# Board4.net
KiCad netlist of a schematic drawn in Altium Designer
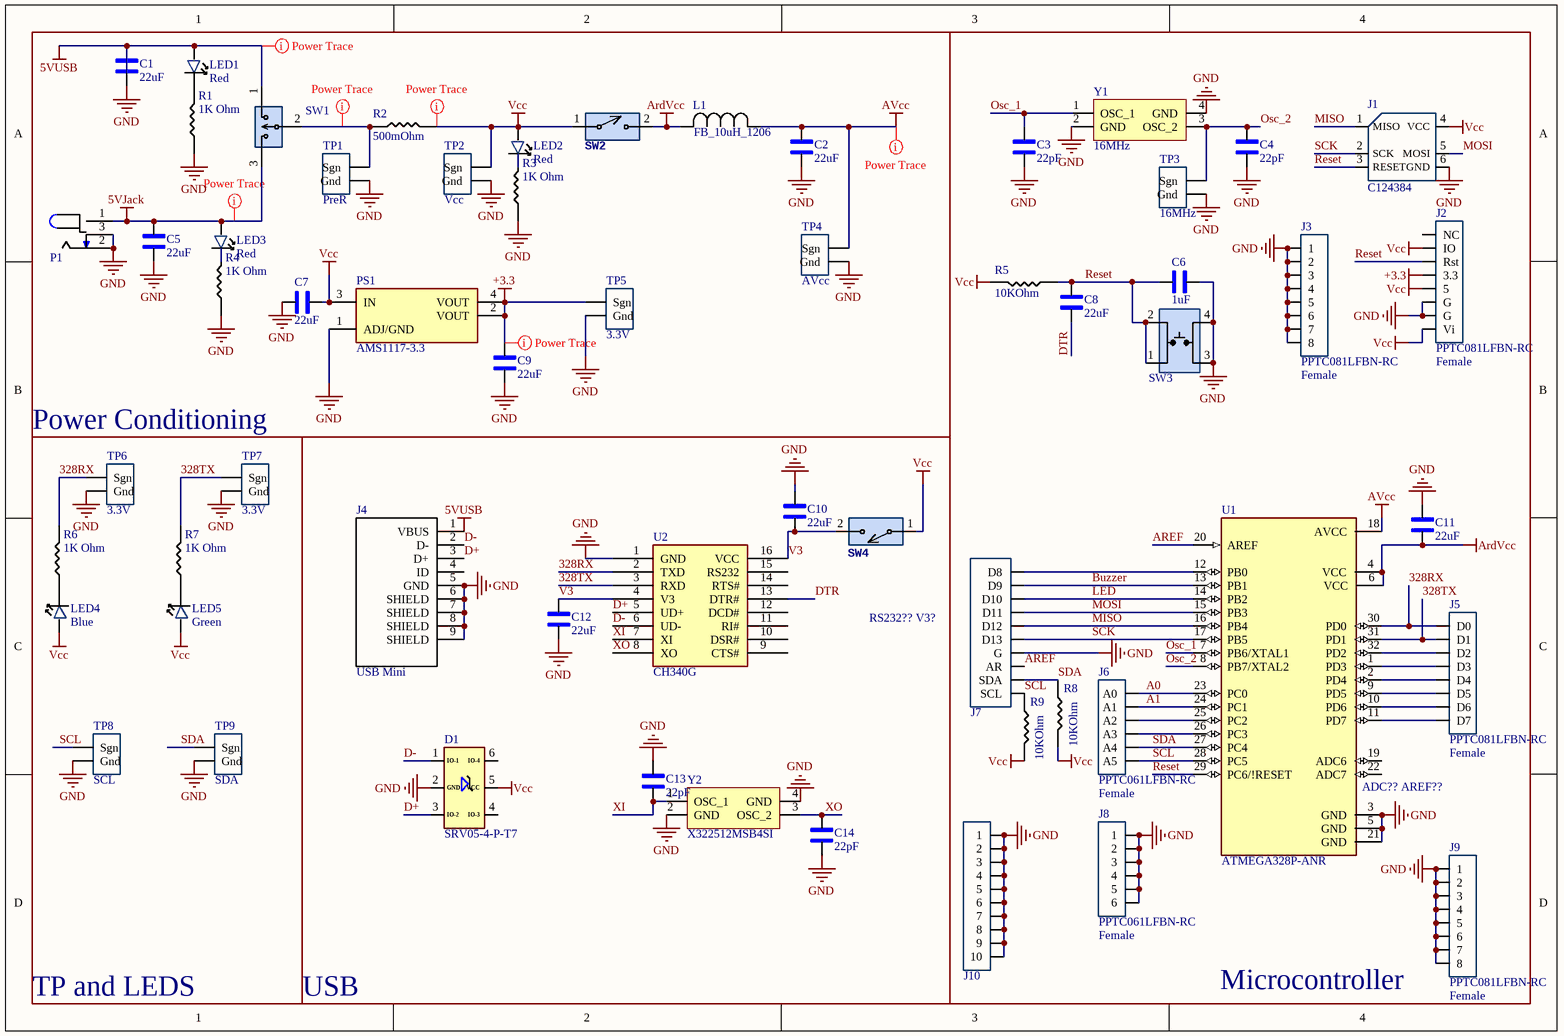
[diagram p0: Board4.SchDoc]

(export (version "E")
  (design (tool "Eeschema 10.0.6"))
  (components
    (comp (ref "C1")
      (value "22uF")
      (footprint "1206_Passive_Capacitor")
      (description "22uF ±10% 25V X5R 1206 Multilayer Ceramic Capacitors MLCC - SMD/SMT RoHS")
      (fields (field (name "MFR PART #") "CL31A226KAHNNNE") (field (name "LCSC PART#") "C12891"))
      (libsource (lib "ECEN5730Lib_2023_01_DS") (part "C_22uF_1206"))
    )
    (comp (ref "C2")
      (value "22uF")
      (footprint "1206_Passive_Capacitor")
      (description "22uF ±10% 25V X5R 1206 Multilayer Ceramic Capacitors MLCC - SMD/SMT RoHS")
      (fields (field (name "MFR PART #") "CL31A226KAHNNNE") (field (name "LCSC PART#") "C12891"))
      (libsource (lib "ECEN5730Lib_2023_01_DS") (part "C_22uF_1206"))
    )
    (comp (ref "C3")
      (value "22pF")
      (footprint "1206_Passive_Capacitor")
      (description "22pF ±5% 1kV C0G 1206 Multilayer Ceramic Capacitors MLCC - SMD/SMT RoHS")
      (fields (field (name "LCSC PART#") "C313096") (field (name "MFR PART #") "1206CG220J102NT"))
      (libsource (lib "ECEN5730Lib_2023_01_DS") (part "C_22pF_1206"))
    )
    (comp (ref "C4")
      (value "22pF")
      (footprint "1206_Passive_Capacitor")
      (description "22pF ±5% 1kV C0G 1206 Multilayer Ceramic Capacitors MLCC - SMD/SMT RoHS")
      (fields (field (name "LCSC PART#") "C313096") (field (name "MFR PART #") "1206CG220J102NT"))
      (libsource (lib "ECEN5730Lib_2023_01_DS") (part "C_22pF_1206"))
    )
    (comp (ref "C5")
      (value "22uF")
      (footprint "1206_Passive_Capacitor")
      (description "22uF ±10% 25V X5R 1206 Multilayer Ceramic Capacitors MLCC - SMD/SMT RoHS")
      (fields (field (name "MFR PART #") "CL31A226KAHNNNE") (field (name "LCSC PART#") "C12891"))
      (libsource (lib "ECEN5730Lib_2023_01_DS") (part "C_22uF_1206"))
    )
    (comp (ref "C6")
      (value "1uF")
      (footprint "1206_Passive_Capacitor")
      (description "MULTILAYER CERAMIC CAPACITORS MLCC - SMD/SMT 1UF 50V 1206 ROHS")
      (fields (field (name "MFR PART #") "CL31B105KBHNNNE") (field (name "LCSC PART#") "C1848"))
      (libsource (lib "ECEN5730Lib_2023_01_DS") (part "C_1uF_1206"))
    )
    (comp (ref "C7")
      (value "22uF")
      (footprint "1206_Passive_Capacitor")
      (description "22uF ±10% 25V X5R 1206 Multilayer Ceramic Capacitors MLCC - SMD/SMT RoHS")
      (fields (field (name "MFR PART #") "CL31A226KAHNNNE") (field (name "LCSC PART#") "C12891"))
      (libsource (lib "ECEN5730Lib_2023_01_DS") (part "C_22uF_1206"))
    )
    (comp (ref "C8")
      (value "22uF")
      (footprint "1206_Passive_Capacitor")
      (description "22uF ±10% 25V X5R 1206 Multilayer Ceramic Capacitors MLCC - SMD/SMT RoHS")
      (fields (field (name "MFR PART #") "CL31A226KAHNNNE") (field (name "LCSC PART#") "C12891"))
      (libsource (lib "ECEN5730Lib_2023_01_DS") (part "C_22uF_1206"))
    )
    (comp (ref "C9")
      (value "22uF")
      (footprint "1206_Passive_Capacitor")
      (description "22uF ±10% 25V X5R 1206 Multilayer Ceramic Capacitors MLCC - SMD/SMT RoHS")
      (fields (field (name "MFR PART #") "CL31A226KAHNNNE") (field (name "LCSC PART#") "C12891"))
      (libsource (lib "ECEN5730Lib_2023_01_DS") (part "C_22uF_1206"))
    )
    (comp (ref "C10")
      (value "22uF")
      (footprint "1206_Passive_Capacitor")
      (description "22uF ±10% 25V X5R 1206 Multilayer Ceramic Capacitors MLCC - SMD/SMT RoHS")
      (fields (field (name "MFR PART #") "CL31A226KAHNNNE") (field (name "LCSC PART#") "C12891"))
      (libsource (lib "ECEN5730Lib_2023_01_DS") (part "C_22uF_1206"))
    )
    (comp (ref "C11")
      (value "22uF")
      (footprint "1206_Passive_Capacitor")
      (description "22uF ±10% 25V X5R 1206 Multilayer Ceramic Capacitors MLCC - SMD/SMT RoHS")
      (fields (field (name "MFR PART #") "CL31A226KAHNNNE") (field (name "LCSC PART#") "C12891"))
      (libsource (lib "ECEN5730Lib_2023_01_DS") (part "C_22uF_1206"))
    )
    (comp (ref "C12")
      (value "22uF")
      (footprint "1206_Passive_Capacitor")
      (description "22uF ±10% 25V X5R 1206 Multilayer Ceramic Capacitors MLCC - SMD/SMT RoHS")
      (fields (field (name "MFR PART #") "CL31A226KAHNNNE") (field (name "LCSC PART#") "C12891"))
      (libsource (lib "ECEN5730Lib_2023_01_DS") (part "C_22uF_1206"))
    )
    (comp (ref "C13")
      (value "22pF")
      (footprint "1206_Passive_Capacitor")
      (description "22pF ±5% 1kV C0G 1206 Multilayer Ceramic Capacitors MLCC - SMD/SMT RoHS")
      (fields (field (name "LCSC PART#") "C313096") (field (name "MFR PART #") "1206CG220J102NT"))
      (libsource (lib "ECEN5730Lib_2023_01_DS") (part "C_22pF_1206"))
    )
    (comp (ref "C14")
      (value "22pF")
      (footprint "1206_Passive_Capacitor")
      (description "22pF ±5% 1kV C0G 1206 Multilayer Ceramic Capacitors MLCC - SMD/SMT RoHS")
      (fields (field (name "LCSC PART#") "C313096") (field (name "MFR PART #") "1206CG220J102NT"))
      (libsource (lib "ECEN5730Lib_2023_01_DS") (part "C_22pF_1206"))
    )
    (comp (ref "D1")
      (value "SRV05-4-P-T7")
      (footprint "TVS")
      (description "TVS SOT-23-6 ROHS")
      (fields (field (name "LCSC PART#") "C85364"))
      (libsource (lib "ECEN5730Lib_2023_01_DS") (part "D_TVS_Diode"))
    )
    (comp (ref "J1")
      (value "NRPN032PAEN-RC")
      (footprint "ICSP")
      (description "Connector Header Through Hole 6 position 0.079\" (2.00mm)")
      (fields (field (name "LCSC PART#") "C124384"))
      (libsource (lib "ECEN5730Lib_2023_01_DS") (part "J_ICSP"))
    )
    (comp (ref "J2")
      (value "PPTC081LFBN-RC")
      (footprint "8_PIN_ARD-PWR_100MIL")
      (description "8 Position Header Connector 0.100\" (2.54mm) Through Hole Tin")
      (fields (field (name "LCSC PART#") "C27438") (field (name "ALTIUM_VALUE") "Female"))
      (libsource (lib "ECEN5730Lib_2023_01_DS") (part "JF_8_PIN_FEMALE_ARD-Pwr"))
    )
    (comp (ref "J3")
      (value "PPTC081LFBN-RC")
      (footprint "8_PIN_100MIL - Female")
      (description "8 Position Header Connector 0.100\" (2.54mm) Through Hole Tin")
      (fields (field (name "LCSC PART#") "C27438") (field (name "ALTIUM_VALUE") "Female"))
      (libsource (lib "ECEN5730Lib_2023_01_DS") (part "JF_8_PIN_FEMALE"))
    )
    (comp (ref "J4")
      (value "USB Mini")
      (footprint "USB_MINI_B")
      (description "Through Hole USB Connectors RoHS")
      (fields (field (name "LCSC PART#") "C46398") (field (name "MFR PART #") "920-462A2021D10102"))
      (libsource (lib "ECEN5730Lib_2023_01_DS") (part "J_USB_B_Mini"))
    )
    (comp (ref "J5")
      (value "PPTC081LFBN-RC")
      (footprint "8_PIN_ARD-DIG_100MIL")
      (description "8 Position Header Connector 0.100\" (2.54mm) Through Hole Tin")
      (fields (field (name "LCSC PART#") "C27438") (field (name "ALTIUM_VALUE") "Female"))
      (libsource (lib "ECEN5730Lib_2023_01_DS") (part "JF_8_PIN_FEMALE_ARD-Dig"))
    )
    (comp (ref "J6")
      (value "PPTC061LFBN-RC")
      (footprint "6_PIN_ARD-Analog_100mil")
      (description "6 Position Header Connector 0.100\" (2.54mm) Through Hole Tin")
      (fields (field (name "LCSC PART#") "C40877") (field (name "ALTIUM_VALUE") "Female"))
      (libsource (lib "ECEN5730Lib_2023_01_DS") (part "JF_6_PIN_FEMALE_ARD-Anolog"))
    )
    (comp (ref "J7")
      (value "PPTC101LFBN-RC")
      (footprint "10_PIN_ARDUINO_100MIL")
      (description "10 Position Header Connector 0.100\" (2.54mm) Through Hole Tin")
      (fields (field (name "LCSC PART#") "C225507"))
      (libsource (lib "ECEN5730Lib_2023_01_DS") (part "JF_10_PIN_FEMALE_ARDUINO"))
    )
    (comp (ref "J8")
      (value "PPTC061LFBN-RC")
      (footprint "6_PIN_100MIL -Female")
      (description "6 Position Header Connector 0.100\" (2.54mm) Through Hole Tin")
      (fields (field (name "LCSC PART#") "C40877") (field (name "ALTIUM_VALUE") "Female"))
      (libsource (lib "ECEN5730Lib_2023_01_DS") (part "JF_6_PIN_FEMALE"))
    )
    (comp (ref "J9")
      (value "PPTC081LFBN-RC")
      (footprint "8_PIN_100MIL - Female")
      (description "8 Position Header Connector 0.100\" (2.54mm) Through Hole Tin")
      (fields (field (name "LCSC PART#") "C27438") (field (name "ALTIUM_VALUE") "Female"))
      (libsource (lib "ECEN5730Lib_2023_01_DS") (part "JF_8_PIN_FEMALE"))
    )
    (comp (ref "J10")
      (value "PPTC101LFBN-RC")
      (footprint "10_PIN_100MIL - Female")
      (description "10 Position Header Connector 0.100\" (2.54mm) Through Hole Tin")
      (fields (field (name "LCSC PART#") "C225507"))
      (libsource (lib "ECEN5730Lib_2023_01_DS") (part "JF_10_PIN_FEMALE_"))
    )
    (comp (ref "L1")
      (value "FB_10uH_1206")
      (footprint "AIML-1206_ABR-M")
      (description "25mA 10uH ±10% 800mΩ 1206  Inductors (SMD) ROHS")
      (fields (field (name "MFR PART #") "CMI321609X100KT") (field (name "LCSC PART#") "C1051"))
      (libsource (lib "ECEN5730Lib_2023_01_DS") (part "FB_10uH_1206"))
    )
    (comp (ref "LED1")
      (value "Red")
      (footprint "LED_1206")
      (description "Red 621~631nm 1206 Light Emitting Diodes (LED) RoHS")
      (fields (field (name "MFR PART #") "15-21/R6C-FQ1R1B/2T") (field (name "LCSC PART#") "C93133"))
      (libsource (lib "ECEN5730Lib_2023_01_DS") (part "LED_RED_1206"))
    )
    (comp (ref "LED2")
      (value "Red")
      (footprint "LED_1206")
      (description "Red 621~631nm 1206 Light Emitting Diodes (LED) RoHS")
      (fields (field (name "MFR PART #") "15-21/R6C-FQ1R1B/2T") (field (name "LCSC PART#") "C93133"))
      (libsource (lib "ECEN5730Lib_2023_01_DS") (part "LED_RED_1206"))
    )
    (comp (ref "LED3")
      (value "Red")
      (footprint "LED_1206")
      (description "Red 621~631nm 1206 Light Emitting Diodes (LED) RoHS")
      (fields (field (name "MFR PART #") "15-21/R6C-FQ1R1B/2T") (field (name "LCSC PART#") "C93133"))
      (libsource (lib "ECEN5730Lib_2023_01_DS") (part "LED_RED_1206"))
    )
    (comp (ref "LED4")
      (value "Blue")
      (footprint "LED_1206")
      (description "blue 1206  Light Emitting Diodes (LED) ROHS")
      (fields (field (name "MFR PART #") "NCD1206B1") (field (name "LCSC PART#") "C130717"))
      (libsource (lib "ECEN5730Lib_2023_01_DS") (part "LED_BLUE_1206"))
    )
    (comp (ref "LED5")
      (value "Green")
      (footprint "LED_1206")
      (description "Green 513~528nm 1206 Light Emitting Diodes (LED) RoHS")
      (fields (field (name "MFR PART #") "SZYY1206G") (field (name "LCSC PART#") "C434439"))
      (libsource (lib "ECEN5730Lib_2023_01_DS") (part "LED_GREEN_1206"))
    )
    (comp (ref "P1")
      (value "Power Jack")
      (footprint "Power_Jack")
      (description "Power Barrel Connector Jack 2.10mm ID (0.083\"), 5.50mm OD (0.217\") Through Hole, Right Angle")
      (fields (field (name "MFR PART #") "PJ-102A") (field (name "LCSC PART#") "C136744"))
      (libsource (lib "ECEN5730Lib_2023_01_DS") (part "P_Power Jack"))
    )
    (comp (ref "PS1")
      (value "AMS1117-3.3")
      (footprint "LDO")
      (description "LOW DROPOUT REGULATORS(LDO) POSITIVE FIXED 1.3V @ 800MA 15V 3.3V 1A SOT-223 ROHS")
      (fields (field (name "LCSC PART#") "C6186"))
      (libsource (lib "ECEN5730Lib_2023_01_DS") (part "PS_AMS_LDO_3v3"))
    )
    (comp (ref "R1")
      (value "1K Ohm")
      (footprint "1206_Passive_Resitor")
      (description "CHIP RESISTOR - SURFACE MOUNT 1KOHMS ±1% 1/4W 1206 ROHS")
      (fields (field (name "MFR PART #") "RNCP1206FTD1K00CT") (field (name "LCSC PART#") "C4410"))
      (libsource (lib "ECEN5730Lib_2023_01_DS") (part "R_1K_1206"))
    )
    (comp (ref "R2")
      (value "500mOhm")
      (footprint "1206_Passive_Resitor")
      (description "Resistors/Shunt 250mW 500mΩ ±800ppm/℃ ±5% 1206  Current Sense  Resistors ROHS")
      (fields (field (name "MFR PART #") "1206W4J050KT5E") (field (name "LCSC PART#") "C247433"))
      (libsource (lib "ECEN5730Lib_2023_01_DS") (part "R_500mOhm_1206"))
    )
    (comp (ref "R3")
      (value "1K Ohm")
      (footprint "1206_Passive_Resitor")
      (description "CHIP RESISTOR - SURFACE MOUNT 1KOHMS ±1% 1/4W 1206 ROHS")
      (fields (field (name "MFR PART #") "RNCP1206FTD1K00CT") (field (name "LCSC PART#") "C4410"))
      (libsource (lib "ECEN5730Lib_2023_01_DS") (part "R_1K_1206"))
    )
    (comp (ref "R4")
      (value "1K Ohm")
      (footprint "1206_Passive_Resitor")
      (description "CHIP RESISTOR - SURFACE MOUNT 1KOHMS ±1% 1/4W 1206 ROHS")
      (fields (field (name "MFR PART #") "RNCP1206FTD1K00CT") (field (name "LCSC PART#") "C4410"))
      (libsource (lib "ECEN5730Lib_2023_01_DS") (part "R_1K_1206"))
    )
    (comp (ref "R5")
      (value "10KOhm")
      (footprint "1206_Passive_Resitor")
      (description "10 kOhms ±5% 0.25W, 1/4W Chip Resistor 1206 (3216 Metric) Automotive AEC-Q200 Thick Film")
      (fields (field (name "MFR PART #") "RMCF1206FT10K0") (field (name "LCSC PART#") "C17902"))
      (libsource (lib "ECEN5730Lib_2023_01_DS") (part "R_10KOhm_1206"))
    )
    (comp (ref "R6")
      (value "1K Ohm")
      (footprint "1206_Passive_Resitor")
      (description "CHIP RESISTOR - SURFACE MOUNT 1KOHMS ±1% 1/4W 1206 ROHS")
      (fields (field (name "MFR PART #") "RNCP1206FTD1K00CT") (field (name "LCSC PART#") "C4410"))
      (libsource (lib "ECEN5730Lib_2023_01_DS") (part "R_1K_1206"))
    )
    (comp (ref "R7")
      (value "1K Ohm")
      (footprint "1206_Passive_Resitor")
      (description "CHIP RESISTOR - SURFACE MOUNT 1KOHMS ±1% 1/4W 1206 ROHS")
      (fields (field (name "MFR PART #") "RNCP1206FTD1K00CT") (field (name "LCSC PART#") "C4410"))
      (libsource (lib "ECEN5730Lib_2023_01_DS") (part "R_1K_1206"))
    )
    (comp (ref "R8")
      (value "10KOhm")
      (footprint "1206_Passive_Resitor")
      (description "10 kOhms ±5% 0.25W, 1/4W Chip Resistor 1206 (3216 Metric) Automotive AEC-Q200 Thick Film")
      (fields (field (name "MFR PART #") "RMCF1206FT10K0") (field (name "LCSC PART#") "C17902"))
      (libsource (lib "ECEN5730Lib_2023_01_DS") (part "R_10KOhm_1206"))
    )
    (comp (ref "R9")
      (value "10KOhm")
      (footprint "1206_Passive_Resitor")
      (description "10 kOhms ±5% 0.25W, 1/4W Chip Resistor 1206 (3216 Metric) Automotive AEC-Q200 Thick Film")
      (fields (field (name "MFR PART #") "RMCF1206FT10K0") (field (name "LCSC PART#") "C17902"))
      (libsource (lib "ECEN5730Lib_2023_01_DS") (part "R_10KOhm_1206"))
    )
    (comp (ref "SW1")
      (value "PREC003SAAN-RC")
      (footprint "3_PIN_100mil")
      (description "Connector Header Through Hole 3 position 0.100\" (2.54mm)")
      (fields (field (name "LCSC PART#") "C49257"))
      (libsource (lib "ECEN5730Lib_2023_01_DS") (part "SW_3Pin_100mil_Switch"))
    )
    (comp (ref "SW2")
      (value "SW_2Pin_100mil_Switch")
      (footprint "2Pin-Header-Conn")
      (description "2Pin Header")
      (fields (field (name "LCSC PART#") "C124375"))
      (libsource (lib "ECEN5730Lib_2023_01_DS") (part "SW_2Pin_100mil_Switch"))
    )
    (comp (ref "SW3")
      (value "TL3305AF160QG")
      (footprint "Switch_JLC")
      (description "Tactile Switch SPST-NO Top Actuated Surface Mount")
      (fields (field (name "MFR PART #") "KH-4.5X4.5X4.3H-STM") (field (name "LCSC PART#") "C2837550"))
      (libsource (lib "ECEN5730Lib_2023_01_DS") (part "SW_Push_Button_JLC"))
    )
    (comp (ref "SW4")
      (value "SW_2Pin_100mil_Switch")
      (footprint "2Pin-Header-Conn")
      (description "2Pin Header")
      (fields (field (name "LCSC PART#") "C124375"))
      (libsource (lib "") (part "SW_2Pin_100mil_Switch_1"))
    )
    (comp (ref "TP1")
      (value "PreR")
      (footprint "TP10x_Probe")
      (description "Test Point 300 mil centers")
      (libsource (lib "") (part "TP_10x_Probe_1"))
    )
    (comp (ref "TP2")
      (value "Vcc")
      (footprint "TP10x_Probe")
      (description "Test Point 300 mil centers")
      (libsource (lib "") (part "TP_10x_Probe_1"))
    )
    (comp (ref "TP3")
      (value "16MHz")
      (footprint "TP10x_Probe")
      (description "Test Point 300 mil centers")
      (libsource (lib "") (part "TP_10x_Probe_1"))
    )
    (comp (ref "TP4")
      (value "AVcc")
      (footprint "TP10x_Probe")
      (description "Test Point 300 mil centers")
      (libsource (lib "") (part "TP_10x_Probe_1"))
    )
    (comp (ref "TP5")
      (value "3.3V")
      (footprint "TP10x_Probe")
      (description "Test Point 300 mil centers")
      (libsource (lib "ECEN5730Lib_2023_01_DS") (part "TP_10x_Probe"))
    )
    (comp (ref "TP6")
      (value "3.3V")
      (footprint "TP10x_Probe")
      (description "Test Point 300 mil centers")
      (libsource (lib "ECEN5730Lib_2023_01_DS") (part "TP_10x_Probe"))
    )
    (comp (ref "TP7")
      (value "3.3V")
      (footprint "TP10x_Probe")
      (description "Test Point 300 mil centers")
      (libsource (lib "ECEN5730Lib_2023_01_DS") (part "TP_10x_Probe"))
    )
    (comp (ref "TP8")
      (value "SCL")
      (footprint "TP10x_Probe")
      (description "Test Point 300 mil centers")
      (libsource (lib "ECEN5730Lib_2023_01_DS") (part "TP_10x_Probe"))
    )
    (comp (ref "TP9")
      (value "SDA")
      (footprint "TP10x_Probe")
      (description "Test Point 300 mil centers")
      (libsource (lib "ECEN5730Lib_2023_01_DS") (part "TP_10x_Probe"))
    )
    (comp (ref "U1")
      (value "ATMEGA328P-ANR")
      (footprint "ATMega328P")
      (description "AVR AVR® ATmega Microcontroller IC 8-Bit 20MHz 32KB (16K x 16) FLASH 32-TQFP (7x7)")
      (fields (field (name "MFR PART #") "ATMEGA328P-AU") (field (name "LCSC PART#") "C14877"))
      (libsource (lib "ECEN5730Lib_2023_01_DS") (part "U_ATMega328P"))
    )
    (comp (ref "U2")
      (value "CH340G")
      (footprint "USB to serial")
      (description "Transceiver USB 2.0 2Mbps SOP-16_150mil USB ICs RoHS")
      (fields (field (name "LCSC PART#") "C14267"))
      (libsource (lib "ECEN5730Lib_2023_01_DS") (part "U_USBtoSerial"))
    )
    (comp (ref "Y1")
      (value "16MHz")
      (footprint "Crystal resonator")
      (description "±10ppm 16000000Hz -40℃~85℃ 贴片无源晶振 60Ω 9pF SMD3225-4P Crystals ROHS")
      (fields (field (name "LCSC PART#") "C13738") (field (name "MFR PART #") "X322516MLB4SI"))
      (libsource (lib "ECEN5730Lib_2023_01_DS") (part "X_16Mhz_Res"))
    )
    (comp (ref "Y2")
      (value "X322512MSB4SI")
      (footprint "Crystal resonator")
      (description "SMD Crystal Resonators 12MHz ±10ppm SMD-3225_4P RoHS")
      (fields (field (name "LCSC PART#") "C9002"))
      (libsource (lib "ECEN5730Lib_2023_01_DS") (part "X_12MHz_Res"))
    )
  )
  (nets
    (net (code "1") (name "+3.3") (class "Default")
      (node (ref "C9") (pin "2") (pinfunction "2_2") (pintype "passive"))
      (node (ref "J2") (pin "4") (pinfunction "3.3_4") (pintype "passive"))
      (node (ref "PS1") (pin "2") (pinfunction "VOUT_2") (pintype "power_in"))
      (node (ref "PS1") (pin "4") (pinfunction "VOUT_4") (pintype "power_in"))
      (node (ref "TP5") (pin "1") (pinfunction "Sgn_1") (pintype "passive"))
    )
    (net (code "2") (name "/328RX") (class "Default")
      (node (ref "J5") (pin "8") (pinfunction "D0_8") (pintype "passive"))
      (node (ref "R6") (pin "2") (pinfunction "2_2") (pintype "passive"))
      (node (ref "TP6") (pin "1") (pinfunction "Sgn_1") (pintype "passive"))
      (node (ref "U1") (pin "30") (pinfunction "PD0_30") (pintype "bidirectional"))
      (node (ref "U2") (pin "2") (pinfunction "TXD_2") (pintype "passive"))
    )
    (net (code "3") (name "/328TX") (class "Default")
      (node (ref "J5") (pin "7") (pinfunction "D1_7") (pintype "passive"))
      (node (ref "R7") (pin "2") (pinfunction "2_2") (pintype "passive"))
      (node (ref "TP7") (pin "1") (pinfunction "Sgn_1") (pintype "passive"))
      (node (ref "U1") (pin "31") (pinfunction "PD1_31") (pintype "bidirectional"))
      (node (ref "U2") (pin "3") (pinfunction "RXD_3") (pintype "passive"))
    )
    (net (code "4") (name "/A0") (class "Default")
      (node (ref "J6") (pin "1") (pinfunction "A0_1") (pintype "passive"))
      (node (ref "U1") (pin "23") (pinfunction "PC0_23") (pintype "bidirectional"))
    )
    (net (code "5") (name "/A1") (class "Default")
      (node (ref "J6") (pin "2") (pinfunction "A1_2") (pintype "passive"))
      (node (ref "U1") (pin "24") (pinfunction "PC1_24") (pintype "bidirectional"))
    )
    (net (code "6") (name "/AREF") (class "Default")
      (node (ref "J7") (pin "3") (pinfunction "AR_3") (pintype "passive"))
      (node (ref "U1") (pin "20") (pinfunction "AREF_20") (pintype "input"))
    )
    (net (code "7") (name "/Buzzer") (class "Default")
      (node (ref "J7") (pin "9") (pinfunction "D9_9") (pintype "passive"))
      (node (ref "U1") (pin "13") (pinfunction "PB1_13") (pintype "bidirectional"))
    )
    (net (code "8") (name "/D+") (class "Default")
      (node (ref "D1") (pin "3") (pinfunction "IO-2_3") (pintype "passive"))
      (node (ref "J4") (pin "3") (pinfunction "D+_3") (pintype "passive"))
      (node (ref "U2") (pin "5") (pinfunction "UD+_5") (pintype "passive"))
    )
    (net (code "9") (name "/D-") (class "Default")
      (node (ref "D1") (pin "1") (pinfunction "IO-1_1") (pintype "passive"))
      (node (ref "J4") (pin "2") (pinfunction "D-_2") (pintype "passive"))
      (node (ref "U2") (pin "6") (pinfunction "UD-_6") (pintype "passive"))
    )
    (net (code "10") (name "/DTR") (class "Default")
      (node (ref "C8") (pin "2") (pinfunction "2_2") (pintype "passive"))
      (node (ref "U2") (pin "13") (pinfunction "DTR#_13") (pintype "passive"))
    )
    (net (code "11") (name "/LED") (class "Default")
      (node (ref "J7") (pin "8") (pinfunction "D10_8") (pintype "passive"))
      (node (ref "U1") (pin "14") (pinfunction "PB2_14") (pintype "bidirectional"))
    )
    (net (code "12") (name "/MISO") (class "Default")
      (node (ref "J1") (pin "1") (pinfunction "MISO_1") (pintype "passive"))
      (node (ref "J7") (pin "6") (pinfunction "D12_6") (pintype "passive"))
      (node (ref "U1") (pin "16") (pinfunction "PB4_16") (pintype "bidirectional"))
    )
    (net (code "13") (name "/MOSI") (class "Default")
      (node (ref "J1") (pin "5") (pinfunction "MOSI_5") (pintype "passive"))
      (node (ref "J7") (pin "7") (pinfunction "D11_7") (pintype "passive"))
      (node (ref "U1") (pin "15") (pinfunction "PB3_15") (pintype "bidirectional"))
    )
    (net (code "14") (name "/Osc_1") (class "Default")
      (node (ref "C3") (pin "2") (pinfunction "2_2") (pintype "passive"))
      (node (ref "U1") (pin "7") (pinfunction "PB6/XTAL1_7") (pintype "bidirectional"))
      (node (ref "Y1") (pin "1") (pinfunction "OSC_1_1") (pintype "passive"))
    )
    (net (code "15") (name "/Osc_2") (class "Default")
      (node (ref "C4") (pin "2") (pinfunction "2_2") (pintype "passive"))
      (node (ref "TP3") (pin "1") (pinfunction "Sgn_1") (pintype "passive"))
      (node (ref "U1") (pin "8") (pinfunction "PB7/XTAL2_8") (pintype "bidirectional"))
      (node (ref "Y1") (pin "3") (pinfunction "OSC_2_3") (pintype "passive"))
    )
    (net (code "16") (name "/Reset") (class "Default")
      (node (ref "C6") (pin "2") (pinfunction "2_2") (pintype "passive"))
      (node (ref "C8") (pin "1") (pinfunction "1_1") (pintype "passive"))
      (node (ref "J1") (pin "3") (pinfunction "RESET_3") (pintype "passive"))
      (node (ref "J2") (pin "3") (pinfunction "Rst_3") (pintype "passive"))
      (node (ref "R5") (pin "1") (pinfunction "1_1") (pintype "passive"))
      (node (ref "SW3") (pin "1") (pinfunction "1_1") (pintype "passive"))
      (node (ref "SW3") (pin "2") (pinfunction "2_2") (pintype "passive"))
      (node (ref "U1") (pin "29") (pinfunction "PC6/!RESET_29") (pintype "bidirectional"))
    )
    (net (code "17") (name "/SCK") (class "Default")
      (node (ref "J1") (pin "2") (pinfunction "SCK_2") (pintype "passive"))
      (node (ref "J7") (pin "5") (pinfunction "D13_5") (pintype "passive"))
      (node (ref "U1") (pin "17") (pinfunction "PB5_17") (pintype "bidirectional"))
    )
    (net (code "18") (name "/SCL") (class "Default")
      (node (ref "J6") (pin "6") (pinfunction "A5_6") (pintype "passive"))
      (node (ref "J7") (pin "1") (pinfunction "SCL_1") (pintype "passive"))
      (node (ref "R9") (pin "1") (pinfunction "1_1") (pintype "passive"))
      (node (ref "TP8") (pin "1") (pinfunction "Sgn_1") (pintype "passive"))
      (node (ref "U1") (pin "28") (pinfunction "PC5_28") (pintype "bidirectional"))
    )
    (net (code "19") (name "/SDA") (class "Default")
      (node (ref "J6") (pin "5") (pinfunction "A4_5") (pintype "passive"))
      (node (ref "J7") (pin "2") (pinfunction "SDA_2") (pintype "passive"))
      (node (ref "R8") (pin "1") (pinfunction "1_1") (pintype "passive"))
      (node (ref "TP9") (pin "1") (pinfunction "Sgn_1") (pintype "passive"))
      (node (ref "U1") (pin "27") (pinfunction "PC4_27") (pintype "bidirectional"))
    )
    (net (code "20") (name "/V3") (class "Default")
      (node (ref "C10") (pin "2") (pinfunction "2_2") (pintype "passive"))
      (node (ref "C12") (pin "2") (pinfunction "2_2") (pintype "passive"))
      (node (ref "SW4") (pin "2") (pinfunction "2_2") (pintype "passive"))
      (node (ref "U2") (pin "16") (pinfunction "VCC_16") (pintype "passive"))
      (node (ref "U2") (pin "4") (pinfunction "V3_4") (pintype "passive"))
    )
    (net (code "21") (name "/XI") (class "Default")
      (node (ref "C13") (pin "1") (pinfunction "1_1") (pintype "passive"))
      (node (ref "U2") (pin "7") (pinfunction "XI_7") (pintype "passive"))
      (node (ref "Y2") (pin "1") (pinfunction "OSC_1_1") (pintype "passive"))
    )
    (net (code "22") (name "/XO") (class "Default")
      (node (ref "C14") (pin "2") (pinfunction "2_2") (pintype "passive"))
      (node (ref "U2") (pin "8") (pinfunction "XO_8") (pintype "passive"))
      (node (ref "Y2") (pin "3") (pinfunction "OSC_2_3") (pintype "passive"))
    )
    (net (code "23") (name "5VJack") (class "Default")
      (node (ref "C5") (pin "2") (pinfunction "2_2") (pintype "passive"))
      (node (ref "LED3") (pin "1") (pinfunction "1_1") (pintype "passive"))
      (node (ref "P1") (pin "1") (pinfunction "1_1") (pintype "power_in"))
      (node (ref "SW1") (pin "3") (pinfunction "3_3") (pintype "passive"))
    )
    (net (code "24") (name "5VUSB") (class "Default")
      (node (ref "C1") (pin "1") (pinfunction "1_1") (pintype "passive"))
      (node (ref "J4") (pin "1") (pinfunction "VBUS_1") (pintype "passive"))
      (node (ref "LED1") (pin "1") (pinfunction "1_1") (pintype "passive"))
      (node (ref "SW1") (pin "1") (pinfunction "1_1") (pintype "passive"))
    )
    (net (code "25") (name "AVcc") (class "Default")
      (node (ref "C2") (pin "2") (pinfunction "2_2") (pintype "passive"))
      (node (ref "L1") (pin "1") (pinfunction "1_1") (pintype "passive"))
      (node (ref "TP4") (pin "1") (pinfunction "Sgn_1") (pintype "passive"))
      (node (ref "U1") (pin "18") (pinfunction "AVCC_18") (pintype "power_in"))
    )
    (net (code "26") (name "ArdVcc") (class "Default")
      (node (ref "C11") (pin "2") (pinfunction "2_2") (pintype "passive"))
      (node (ref "L1") (pin "2") (pinfunction "2_2") (pintype "passive"))
      (node (ref "SW2") (pin "2") (pinfunction "2_2") (pintype "passive"))
      (node (ref "U1") (pin "4") (pinfunction "VCC_4") (pintype "power_in"))
      (node (ref "U1") (pin "6") (pinfunction "VCC_6") (pintype "power_in"))
    )
    (net (code "27") (name "GND") (class "Default")
      (node (ref "C1") (pin "2") (pinfunction "2_2") (pintype "passive"))
      (node (ref "C10") (pin "1") (pinfunction "1_1") (pintype "passive"))
      (node (ref "C11") (pin "1") (pinfunction "1_1") (pintype "passive"))
      (node (ref "C12") (pin "1") (pinfunction "1_1") (pintype "passive"))
      (node (ref "C13") (pin "2") (pinfunction "2_2") (pintype "passive"))
      (node (ref "C14") (pin "1") (pinfunction "1_1") (pintype "passive"))
      (node (ref "C2") (pin "1") (pinfunction "1_1") (pintype "passive"))
      (node (ref "C3") (pin "1") (pinfunction "1_1") (pintype "passive"))
      (node (ref "C4") (pin "1") (pinfunction "1_1") (pintype "passive"))
      (node (ref "C5") (pin "1") (pinfunction "1_1") (pintype "passive"))
      (node (ref "C6") (pin "1") (pinfunction "1_1") (pintype "passive"))
      (node (ref "C7") (pin "1") (pinfunction "1_1") (pintype "passive"))
      (node (ref "C9") (pin "1") (pinfunction "1_1") (pintype "passive"))
      (node (ref "D1") (pin "2") (pinfunction "GND_2") (pintype "passive"))
      (node (ref "J1") (pin "6") (pinfunction "GND_6") (pintype "passive"))
      (node (ref "J10") (pin "1") (pinfunction "1_1") (pintype "passive"))
      (node (ref "J10") (pin "10") (pinfunction "10_10") (pintype "passive"))
      (node (ref "J10") (pin "2") (pinfunction "2_2") (pintype "passive"))
      (node (ref "J10") (pin "3") (pinfunction "3_3") (pintype "passive"))
      (node (ref "J10") (pin "4") (pinfunction "4_4") (pintype "passive"))
      (node (ref "J10") (pin "5") (pinfunction "5_5") (pintype "passive"))
      (node (ref "J10") (pin "6") (pinfunction "6_6") (pintype "passive"))
      (node (ref "J10") (pin "7") (pinfunction "7_7") (pintype "passive"))
      (node (ref "J10") (pin "8") (pinfunction "8_8") (pintype "passive"))
      (node (ref "J10") (pin "9") (pinfunction "9_9") (pintype "passive"))
      (node (ref "J2") (pin "6") (pinfunction "G_6") (pintype "passive"))
      (node (ref "J2") (pin "7") (pinfunction "G_7") (pintype "passive"))
      (node (ref "J3") (pin "1") (pinfunction "1_1") (pintype "passive"))
      (node (ref "J3") (pin "2") (pinfunction "2_2") (pintype "passive"))
      (node (ref "J3") (pin "3") (pinfunction "3_3") (pintype "passive"))
      (node (ref "J3") (pin "4") (pinfunction "4_4") (pintype "passive"))
      (node (ref "J3") (pin "5") (pinfunction "5_5") (pintype "passive"))
      (node (ref "J3") (pin "6") (pinfunction "6_6") (pintype "passive"))
      (node (ref "J3") (pin "7") (pinfunction "7_7") (pintype "passive"))
      (node (ref "J3") (pin "8") (pinfunction "8_8") (pintype "passive"))
      (node (ref "J4") (pin "5") (pinfunction "GND_5") (pintype "passive"))
      (node (ref "J4") (pin "6") (pinfunction "SHIELD_6") (pintype "passive"))
      (node (ref "J4") (pin "7") (pinfunction "SHIELD_7") (pintype "passive"))
      (node (ref "J4") (pin "8") (pinfunction "SHIELD_8") (pintype "passive"))
      (node (ref "J4") (pin "9") (pinfunction "SHIELD_9") (pintype "passive"))
      (node (ref "J7") (pin "4") (pinfunction "G_4") (pintype "passive"))
      (node (ref "J8") (pin "1") (pinfunction "1_1") (pintype "passive"))
      (node (ref "J8") (pin "2") (pinfunction "2_2") (pintype "passive"))
      (node (ref "J8") (pin "3") (pinfunction "3_3") (pintype "passive"))
      (node (ref "J8") (pin "4") (pinfunction "4_4") (pintype "passive"))
      (node (ref "J8") (pin "5") (pinfunction "5_5") (pintype "passive"))
      (node (ref "J8") (pin "6") (pinfunction "6_6") (pintype "passive"))
      (node (ref "J9") (pin "1") (pinfunction "1_1") (pintype "passive"))
      (node (ref "J9") (pin "2") (pinfunction "2_2") (pintype "passive"))
      (node (ref "J9") (pin "3") (pinfunction "3_3") (pintype "passive"))
      (node (ref "J9") (pin "4") (pinfunction "4_4") (pintype "passive"))
      (node (ref "J9") (pin "5") (pinfunction "5_5") (pintype "passive"))
      (node (ref "J9") (pin "6") (pinfunction "6_6") (pintype "passive"))
      (node (ref "J9") (pin "7") (pinfunction "7_7") (pintype "passive"))
      (node (ref "J9") (pin "8") (pinfunction "8_8") (pintype "passive"))
      (node (ref "P1") (pin "2") (pinfunction "2_2") (pintype "power_in"))
      (node (ref "P1") (pin "3") (pinfunction "3_3") (pintype "power_in"))
      (node (ref "PS1") (pin "1") (pinfunction "ADJ/GND_1") (pintype "passive"))
      (node (ref "R1") (pin "1") (pinfunction "1_1") (pintype "passive"))
      (node (ref "R3") (pin "1") (pinfunction "1_1") (pintype "passive"))
      (node (ref "R4") (pin "1") (pinfunction "1_1") (pintype "passive"))
      (node (ref "SW3") (pin "3") (pinfunction "3_3") (pintype "passive"))
      (node (ref "SW3") (pin "4") (pinfunction "4_4") (pintype "passive"))
      (node (ref "TP1") (pin "2") (pinfunction "Gnd_2") (pintype "passive"))
      (node (ref "TP2") (pin "2") (pinfunction "Gnd_2") (pintype "passive"))
      (node (ref "TP3") (pin "2") (pinfunction "Gnd_2") (pintype "passive"))
      (node (ref "TP4") (pin "2") (pinfunction "Gnd_2") (pintype "passive"))
      (node (ref "TP5") (pin "2") (pinfunction "Gnd_2") (pintype "passive"))
      (node (ref "TP6") (pin "2") (pinfunction "Gnd_2") (pintype "passive"))
      (node (ref "TP7") (pin "2") (pinfunction "Gnd_2") (pintype "passive"))
      (node (ref "TP8") (pin "2") (pinfunction "Gnd_2") (pintype "passive"))
      (node (ref "TP9") (pin "2") (pinfunction "Gnd_2") (pintype "passive"))
      (node (ref "U1") (pin "21") (pinfunction "GND_21") (pintype "power_in"))
      (node (ref "U1") (pin "3") (pinfunction "GND_3") (pintype "power_in"))
      (node (ref "U1") (pin "5") (pinfunction "GND_5") (pintype "power_in"))
      (node (ref "U2") (pin "1") (pinfunction "GND_1") (pintype "passive"))
      (node (ref "Y1") (pin "2") (pinfunction "GND_2") (pintype "passive"))
      (node (ref "Y1") (pin "4") (pinfunction "GND_4") (pintype "passive"))
      (node (ref "Y2") (pin "2") (pinfunction "GND_2") (pintype "passive"))
      (node (ref "Y2") (pin "4") (pinfunction "GND_4") (pintype "passive"))
    )
    (net (code "28") (name "Net-(J5-D2)") (class "Default")
      (node (ref "J5") (pin "6") (pinfunction "D2_6") (pintype "passive"))
      (node (ref "U1") (pin "32") (pinfunction "PD2_32") (pintype "bidirectional"))
    )
    (net (code "29") (name "Net-(J5-D3)") (class "Default")
      (node (ref "J5") (pin "5") (pinfunction "D3_5") (pintype "passive"))
      (node (ref "U1") (pin "1") (pinfunction "PD3_1") (pintype "bidirectional"))
    )
    (net (code "30") (name "Net-(J5-D4)") (class "Default")
      (node (ref "J5") (pin "4") (pinfunction "D4_4") (pintype "passive"))
      (node (ref "U1") (pin "2") (pinfunction "PD4_2") (pintype "bidirectional"))
    )
    (net (code "31") (name "Net-(J5-D5)") (class "Default")
      (node (ref "J5") (pin "3") (pinfunction "D5_3") (pintype "passive"))
      (node (ref "U1") (pin "9") (pinfunction "PD5_9") (pintype "bidirectional"))
    )
    (net (code "32") (name "Net-(J5-D6)") (class "Default")
      (node (ref "J5") (pin "2") (pinfunction "D6_2") (pintype "passive"))
      (node (ref "U1") (pin "10") (pinfunction "PD6_10") (pintype "bidirectional"))
    )
    (net (code "33") (name "Net-(J5-D7)") (class "Default")
      (node (ref "J5") (pin "1") (pinfunction "D7_1") (pintype "passive"))
      (node (ref "U1") (pin "11") (pinfunction "PD7_11") (pintype "bidirectional"))
    )
    (net (code "34") (name "Net-(J6-A2)") (class "Default")
      (node (ref "J6") (pin "3") (pinfunction "A2_3") (pintype "passive"))
      (node (ref "U1") (pin "25") (pinfunction "PC2_25") (pintype "bidirectional"))
    )
    (net (code "35") (name "Net-(J6-A3)") (class "Default")
      (node (ref "J6") (pin "4") (pinfunction "A3_4") (pintype "passive"))
      (node (ref "U1") (pin "26") (pinfunction "PC3_26") (pintype "bidirectional"))
    )
    (net (code "36") (name "Net-(J7-D8)") (class "Default")
      (node (ref "J7") (pin "10") (pinfunction "D8_10") (pintype "passive"))
      (node (ref "U1") (pin "12") (pinfunction "PB0_12") (pintype "bidirectional"))
    )
    (net (code "37") (name "Net-(LED1-Pad2)") (class "Default")
      (node (ref "LED1") (pin "2") (pinfunction "2_2") (pintype "passive"))
      (node (ref "R1") (pin "2") (pinfunction "2_2") (pintype "passive"))
    )
    (net (code "38") (name "Net-(LED2-Pad2)") (class "Default")
      (node (ref "LED2") (pin "2") (pinfunction "2_2") (pintype "passive"))
      (node (ref "R3") (pin "2") (pinfunction "2_2") (pintype "passive"))
    )
    (net (code "39") (name "Net-(LED3-Pad2)") (class "Default")
      (node (ref "LED3") (pin "2") (pinfunction "2_2") (pintype "passive"))
      (node (ref "R4") (pin "2") (pinfunction "2_2") (pintype "passive"))
    )
    (net (code "40") (name "Net-(LED4-Pad2)") (class "Default")
      (node (ref "LED4") (pin "2") (pinfunction "2_2") (pintype "passive"))
      (node (ref "R6") (pin "1") (pinfunction "1_1") (pintype "passive"))
    )
    (net (code "41") (name "Net-(LED5-Pad2)") (class "Default")
      (node (ref "LED5") (pin "2") (pinfunction "2_2") (pintype "passive"))
      (node (ref "R7") (pin "1") (pinfunction "1_1") (pintype "passive"))
    )
    (net (code "42") (name "Net-(TP1-Sgn)") (class "Default")
      (node (ref "R2") (pin "1") (pinfunction "1_1") (pintype "passive"))
      (node (ref "SW1") (pin "2") (pinfunction "2_2") (pintype "passive"))
      (node (ref "TP1") (pin "1") (pinfunction "Sgn_1") (pintype "passive"))
    )
    (net (code "43") (name "Vcc") (class "Default")
      (node (ref "C7") (pin "2") (pinfunction "2_2") (pintype "passive"))
      (node (ref "D1") (pin "5") (pinfunction "VCC_5") (pintype "passive"))
      (node (ref "J1") (pin "4") (pinfunction "VCC_4") (pintype "passive"))
      (node (ref "J2") (pin "2") (pinfunction "IO_2") (pintype "passive"))
      (node (ref "J2") (pin "5") (pinfunction "5_5") (pintype "passive"))
      (node (ref "J2") (pin "8") (pinfunction "Vi_8") (pintype "passive"))
      (node (ref "LED2") (pin "1") (pinfunction "1_1") (pintype "passive"))
      (node (ref "LED4") (pin "1") (pinfunction "1_1") (pintype "passive"))
      (node (ref "LED5") (pin "1") (pinfunction "1_1") (pintype "passive"))
      (node (ref "PS1") (pin "3") (pinfunction "IN_3") (pintype "power_in"))
      (node (ref "R2") (pin "2") (pinfunction "2_2") (pintype "passive"))
      (node (ref "R5") (pin "2") (pinfunction "2_2") (pintype "passive"))
      (node (ref "R8") (pin "2") (pinfunction "2_2") (pintype "passive"))
      (node (ref "R9") (pin "2") (pinfunction "2_2") (pintype "passive"))
      (node (ref "SW2") (pin "1") (pinfunction "1_1") (pintype "passive"))
      (node (ref "SW4") (pin "1") (pinfunction "1_1") (pintype "passive"))
      (node (ref "TP2") (pin "1") (pinfunction "Sgn_1") (pintype "passive"))
    )
    (net (code "44") (name "unconnected-(D1-IO-3-Pad4)") (class "Default")
      (node (ref "D1") (pin "4") (pinfunction "IO-3_4") (pintype "passive"))
    )
    (net (code "45") (name "unconnected-(D1-IO-4-Pad6)") (class "Default")
      (node (ref "D1") (pin "6") (pinfunction "IO-4_6") (pintype "passive"))
    )
    (net (code "46") (name "unconnected-(J2-NC-Pad1)") (class "Default")
      (node (ref "J2") (pin "1") (pinfunction "NC_1") (pintype "passive"))
    )
    (net (code "47") (name "unconnected-(J4-ID-Pad4)") (class "Default")
      (node (ref "J4") (pin "4") (pinfunction "ID_4") (pintype "passive"))
    )
    (net (code "48") (name "unconnected-(U1-ADC6-Pad19)") (class "Default")
      (node (ref "U1") (pin "19") (pinfunction "ADC6_19") (pintype "bidirectional"))
    )
    (net (code "49") (name "unconnected-(U1-ADC7-Pad22)") (class "Default")
      (node (ref "U1") (pin "22") (pinfunction "ADC7_22") (pintype "bidirectional"))
    )
    (net (code "50") (name "unconnected-(U2-CTS#-Pad9)") (class "Default")
      (node (ref "U2") (pin "9") (pinfunction "CTS#_9") (pintype "passive"))
    )
    (net (code "51") (name "unconnected-(U2-DCD#-Pad12)") (class "Default")
      (node (ref "U2") (pin "12") (pinfunction "DCD#_12") (pintype "passive"))
    )
    (net (code "52") (name "unconnected-(U2-DSR#-Pad10)") (class "Default")
      (node (ref "U2") (pin "10") (pinfunction "DSR#_10") (pintype "passive"))
    )
    (net (code "53") (name "unconnected-(U2-RI#-Pad11)") (class "Default")
      (node (ref "U2") (pin "11") (pinfunction "RI#_11") (pintype "passive"))
    )
    (net (code "54") (name "unconnected-(U2-RS232-Pad15)") (class "Default")
      (node (ref "U2") (pin "15") (pinfunction "RS232_15") (pintype "passive"))
    )
    (net (code "55") (name "unconnected-(U2-RTS#-Pad14)") (class "Default")
      (node (ref "U2") (pin "14") (pinfunction "RTS#_14") (pintype "passive"))
    )
  )
)
